# lcd20x4_leds.net
KiCad netlist of a schematic drawn in EAGLE
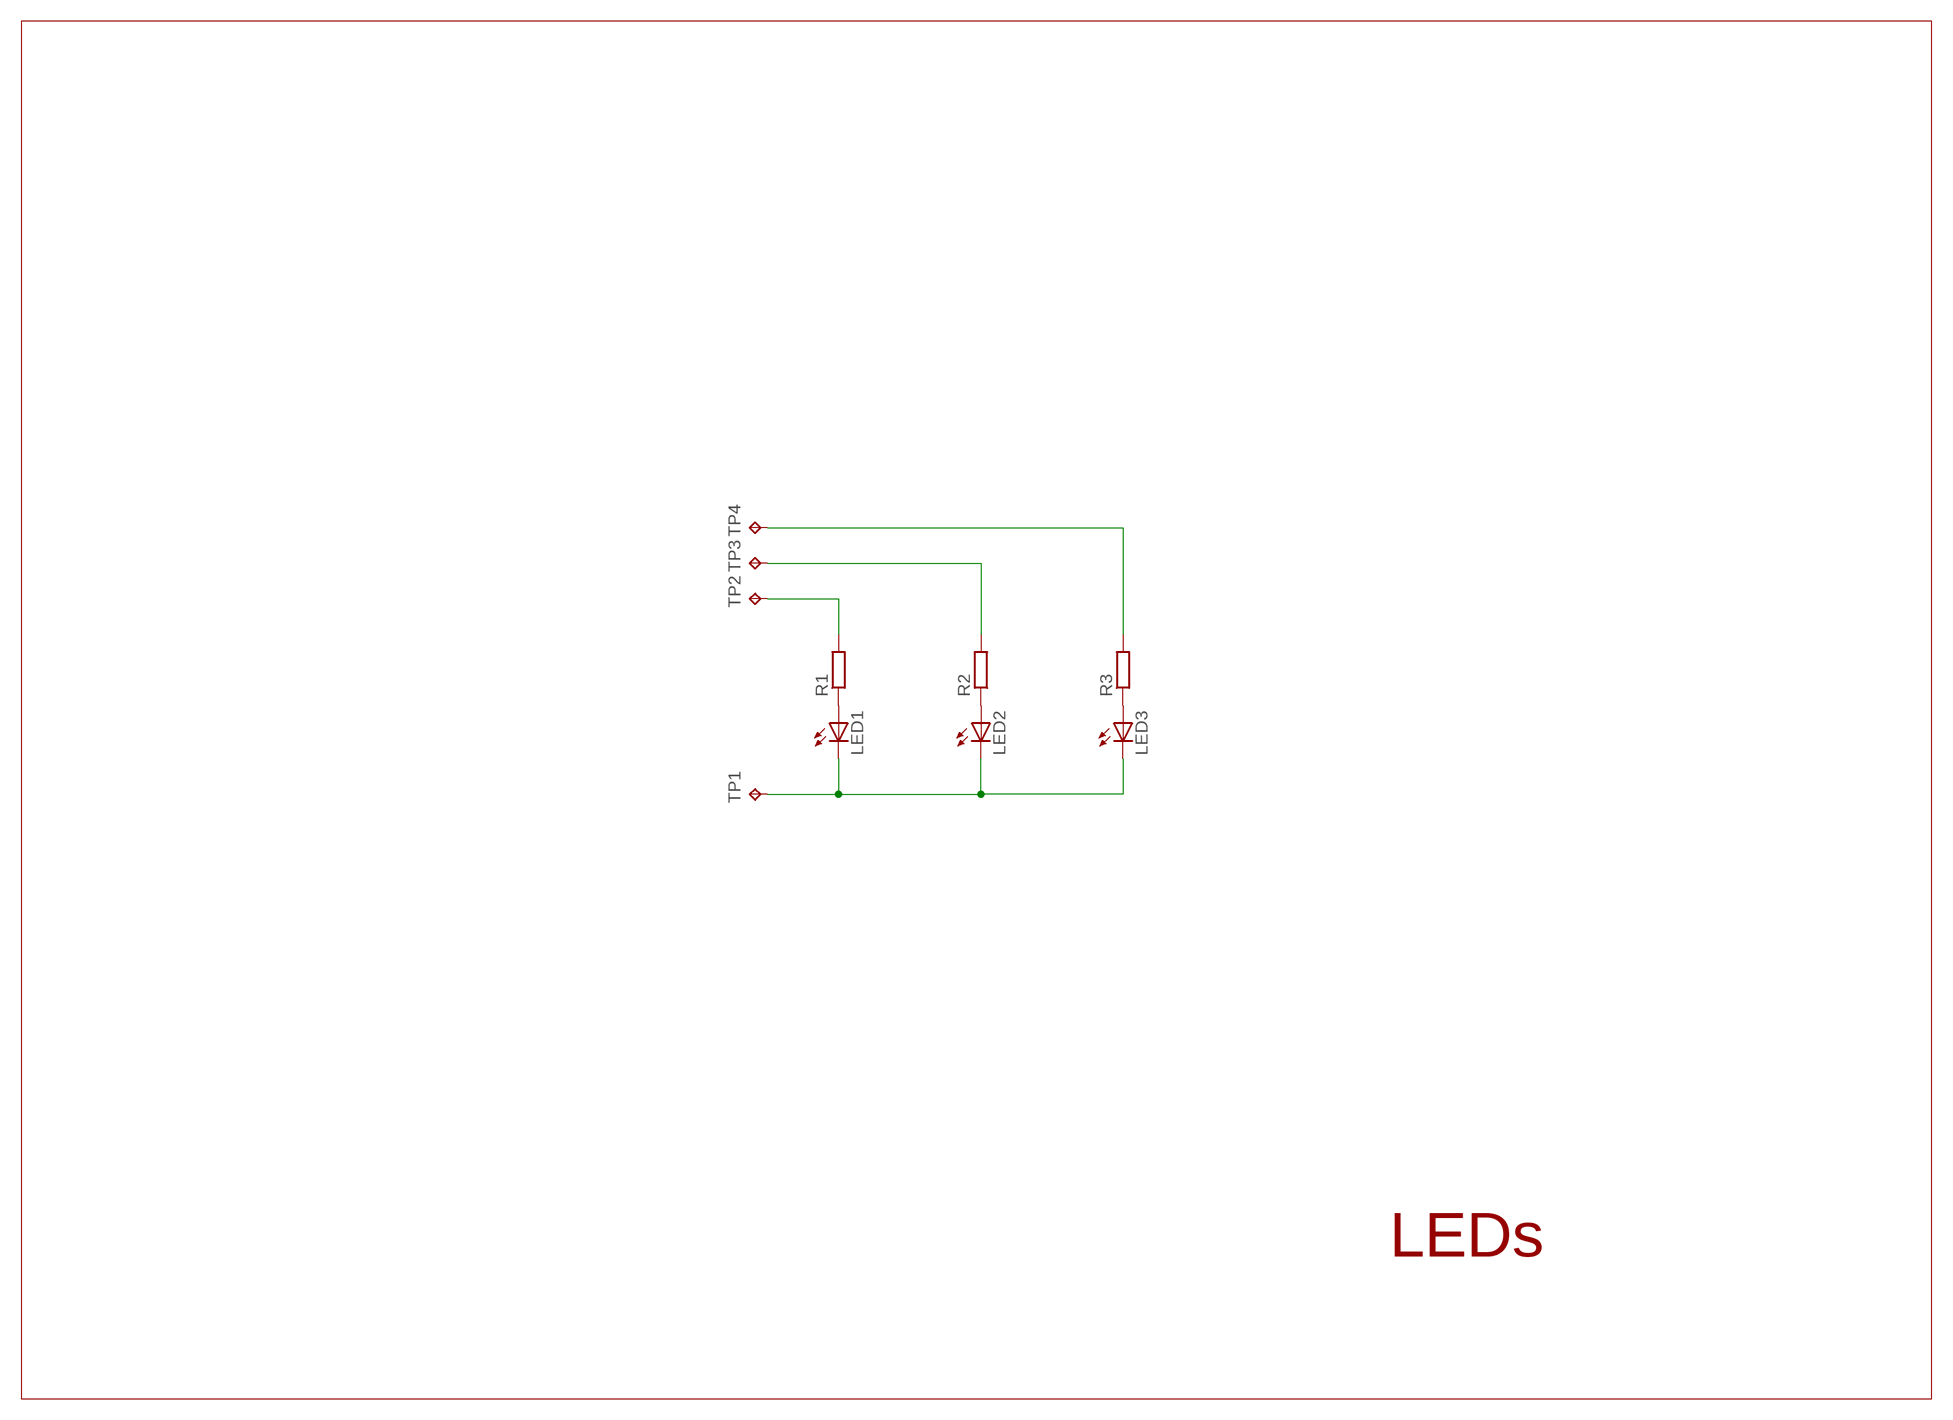
[diagram p0: schematic, sheet 1]

(export (version "E")
  (design (tool "Eeschema 10.0.6"))
  (components
    (comp (ref "LED1")
      (value "LED5MM")
      (footprint "eagle-import:LED5MM")
      (libsource (lib "eagle-import") (part "LED5MM"))
    )
    (comp (ref "LED2")
      (value "LED5MM")
      (footprint "eagle-import:LED5MM")
      (libsource (lib "eagle-import") (part "LED5MM"))
    )
    (comp (ref "LED3")
      (value "LED5MM")
      (footprint "eagle-import:LED5MM")
      (libsource (lib "eagle-import") (part "LED5MM"))
    )
    (comp (ref "R1")
      (value "R-EU_R0805")
      (footprint "eagle-import:R0805")
      (libsource (lib "eagle-import") (part "R-EU_R0805"))
    )
    (comp (ref "R2")
      (value "R-EU_R0805")
      (footprint "eagle-import:R0805")
      (libsource (lib "eagle-import") (part "R-EU_R0805"))
    )
    (comp (ref "R3")
      (value "R-EU_R0805")
      (footprint "eagle-import:R0805")
      (libsource (lib "eagle-import") (part "R-EU_R0805"))
    )
    (comp (ref "TP1")
      (value "TPB1,27")
      (footprint "eagle-import:B1,27")
      (libsource (lib "eagle-import") (part "TPB1,27"))
    )
    (comp (ref "TP2")
      (value "TPB1,27")
      (footprint "eagle-import:B1,27")
      (libsource (lib "eagle-import") (part "TPB1,27"))
    )
    (comp (ref "TP3")
      (value "TPB1,27")
      (footprint "eagle-import:B1,27")
      (libsource (lib "eagle-import") (part "TPB1,27"))
    )
    (comp (ref "TP4")
      (value "TPB1,27")
      (footprint "eagle-import:B1,27")
      (libsource (lib "eagle-import") (part "TPB1,27"))
    )
  )
  (nets
    (net (code "1") (name "Net-(LED1-C)") (class "Default")
      (node (ref "LED1") (pin "K") (pinfunction "C_K") (pintype "passive"))
      (node (ref "LED2") (pin "K") (pinfunction "C_K") (pintype "passive"))
      (node (ref "LED3") (pin "K") (pinfunction "C_K") (pintype "passive"))
      (node (ref "TP1") (pin "TP") (pinfunction "TP_TP") (pintype "input"))
    )
    (net (code "2") (name "Net-(LED1-PadA)") (class "Default")
      (node (ref "LED1") (pin "A") (pinfunction "A_A") (pintype "passive"))
      (node (ref "R1") (pin "1") (pinfunction "1_1") (pintype "passive"))
    )
    (net (code "3") (name "Net-(LED2-PadA)") (class "Default")
      (node (ref "LED2") (pin "A") (pinfunction "A_A") (pintype "passive"))
      (node (ref "R2") (pin "1") (pinfunction "1_1") (pintype "passive"))
    )
    (net (code "4") (name "Net-(LED3-PadA)") (class "Default")
      (node (ref "LED3") (pin "A") (pinfunction "A_A") (pintype "passive"))
      (node (ref "R3") (pin "1") (pinfunction "1_1") (pintype "passive"))
    )
    (net (code "5") (name "Net-(R1-Pad2)") (class "Default")
      (node (ref "R1") (pin "2") (pinfunction "2_2") (pintype "passive"))
      (node (ref "TP2") (pin "TP") (pinfunction "TP_TP") (pintype "input"))
    )
    (net (code "6") (name "Net-(R2-Pad2)") (class "Default")
      (node (ref "R2") (pin "2") (pinfunction "2_2") (pintype "passive"))
      (node (ref "TP3") (pin "TP") (pinfunction "TP_TP") (pintype "input"))
    )
    (net (code "7") (name "Net-(R3-Pad2)") (class "Default")
      (node (ref "R3") (pin "2") (pinfunction "2_2") (pintype "passive"))
      (node (ref "TP4") (pin "TP") (pinfunction "TP_TP") (pintype "input"))
    )
  )
)
